# BB-shield-adapter.net
KiCad netlist of a schematic drawn in EAGLE
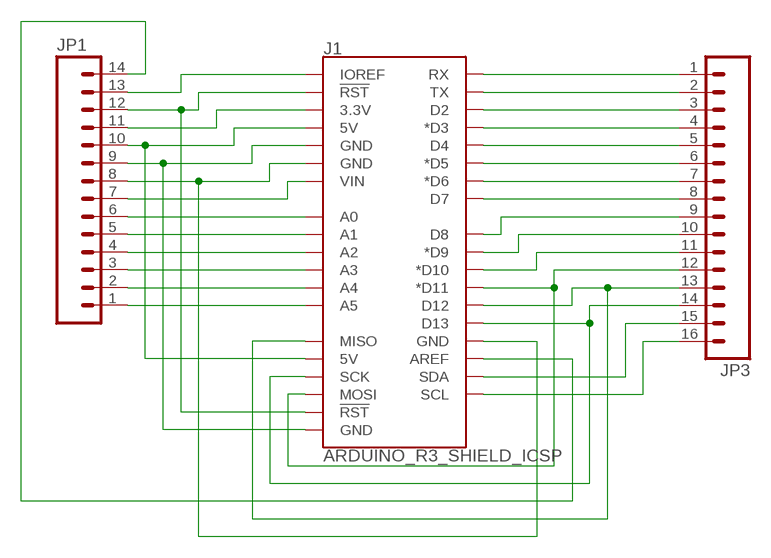
[diagram p0: schematic, sheet 1]

(export (version "E")
  (design (tool "Eeschema 10.0.6"))
  (components
    (comp (ref "J1")
      (value "ARDUINO_R3_SHIELD_ICSP")
      (footprint "eagle-import:UNO_R3_SHIELD_ICSP")
      (libsource (lib "eagle-import") (part "ARDUINO_R3_SHIELD_ICSP"))
    )
    (comp (ref "JP1")
      (value "M14")
      (footprint "eagle-import:1X14")
      (libsource (lib "eagle-import") (part "M14"))
    )
    (comp (ref "JP3")
      (value "M16PTH")
      (footprint "eagle-import:1X16")
      (libsource (lib "eagle-import") (part "M16PTH"))
    )
  )
  (nets
    (net (code "1") (name "Net-(J1-*D3)") (class "Default")
      (node (ref "J1") (pin "D3") (pinfunction "*D3_D3") (pintype "bidirectional"))
      (node (ref "JP3") (pin "4") (pinfunction "4_4") (pintype "passive"))
    )
    (net (code "2") (name "Net-(J1-*D5)") (class "Default")
      (node (ref "J1") (pin "D5") (pinfunction "*D5_D5") (pintype "bidirectional"))
      (node (ref "JP3") (pin "6") (pinfunction "6_6") (pintype "passive"))
    )
    (net (code "3") (name "Net-(J1-*D6)") (class "Default")
      (node (ref "J1") (pin "D6") (pinfunction "*D6_D6") (pintype "bidirectional"))
      (node (ref "JP3") (pin "7") (pinfunction "7_7") (pintype "passive"))
    )
    (net (code "4") (name "Net-(J1-*D9)") (class "Default")
      (node (ref "J1") (pin "D9") (pinfunction "*D9_D9") (pintype "bidirectional"))
      (node (ref "JP3") (pin "10") (pinfunction "10_10") (pintype "passive"))
    )
    (net (code "5") (name "Net-(J1-*D10)") (class "Default")
      (node (ref "J1") (pin "D10") (pinfunction "*D10_D10") (pintype "bidirectional"))
      (node (ref "JP3") (pin "11") (pinfunction "11_11") (pintype "passive"))
    )
    (net (code "6") (name "Net-(J1-*D11)") (class "Default")
      (node (ref "J1") (pin "D11") (pinfunction "*D11_D11") (pintype "bidirectional"))
      (node (ref "J1") (pin "MOSI") (pinfunction "MOSI_MOSI") (pintype "bidirectional"))
      (node (ref "JP3") (pin "12") (pinfunction "12_12") (pintype "passive"))
    )
    (net (code "7") (name "Net-(J1-5V-Pad5V_ICSP)") (class "Default")
      (node (ref "J1") (pin "5V") (pinfunction "5V_5V") (pintype "bidirectional"))
      (node (ref "J1") (pin "5V_ICSP") (pinfunction "5V_5V_ICSP") (pintype "bidirectional"))
      (node (ref "JP1") (pin "10") (pinfunction "10_10") (pintype "passive"))
    )
    (net (code "8") (name "Net-(J1-GND-PadGND@0)") (class "Default")
      (node (ref "J1") (pin "GND@0") (pinfunction "GND_GND@0") (pintype "bidirectional"))
      (node (ref "J1") (pin "GND_ICSP") (pinfunction "GND_GND_ICSP") (pintype "bidirectional"))
      (node (ref "JP1") (pin "9") (pinfunction "9_9") (pintype "passive"))
    )
    (net (code "9") (name "Net-(J1-GND-PadGND@1)") (class "Default")
      (node (ref "J1") (pin "GND@1") (pinfunction "GND_GND@1") (pintype "bidirectional"))
      (node (ref "J1") (pin "GND@2") (pinfunction "GND_GND@2") (pintype "bidirectional"))
      (node (ref "JP1") (pin "8") (pinfunction "8_8") (pintype "passive"))
    )
    (net (code "10") (name "Net-(J1-Pad3.3V)") (class "Default")
      (node (ref "J1") (pin "3.3V") (pinfunction "3.3V_3.3V") (pintype "bidirectional"))
      (node (ref "JP1") (pin "11") (pinfunction "11_11") (pintype "passive"))
    )
    (net (code "11") (name "Net-(J1-PadA0)") (class "Default")
      (node (ref "J1") (pin "A0") (pinfunction "A0_A0") (pintype "bidirectional"))
      (node (ref "JP1") (pin "6") (pinfunction "6_6") (pintype "passive"))
    )
    (net (code "12") (name "Net-(J1-PadA1)") (class "Default")
      (node (ref "J1") (pin "A1") (pinfunction "A1_A1") (pintype "bidirectional"))
      (node (ref "JP1") (pin "5") (pinfunction "5_5") (pintype "passive"))
    )
    (net (code "13") (name "Net-(J1-PadA2)") (class "Default")
      (node (ref "J1") (pin "A2") (pinfunction "A2_A2") (pintype "bidirectional"))
      (node (ref "JP1") (pin "4") (pinfunction "4_4") (pintype "passive"))
    )
    (net (code "14") (name "Net-(J1-PadA3)") (class "Default")
      (node (ref "J1") (pin "A3") (pinfunction "A3_A3") (pintype "bidirectional"))
      (node (ref "JP1") (pin "3") (pinfunction "3_3") (pintype "passive"))
    )
    (net (code "15") (name "Net-(J1-PadA4)") (class "Default")
      (node (ref "J1") (pin "A4") (pinfunction "A4_A4") (pintype "bidirectional"))
      (node (ref "JP1") (pin "2") (pinfunction "2_2") (pintype "passive"))
    )
    (net (code "16") (name "Net-(J1-PadA5)") (class "Default")
      (node (ref "J1") (pin "A5") (pinfunction "A5_A5") (pintype "bidirectional"))
      (node (ref "JP1") (pin "1") (pinfunction "1_1") (pintype "passive"))
    )
    (net (code "17") (name "Net-(J1-PadAREF)") (class "Default")
      (node (ref "J1") (pin "AREF") (pinfunction "AREF_AREF") (pintype "bidirectional"))
      (node (ref "JP1") (pin "14") (pinfunction "14_14") (pintype "passive"))
    )
    (net (code "18") (name "Net-(J1-PadD2)") (class "Default")
      (node (ref "J1") (pin "D2") (pinfunction "D2_D2") (pintype "bidirectional"))
      (node (ref "JP3") (pin "3") (pinfunction "3_3") (pintype "passive"))
    )
    (net (code "19") (name "Net-(J1-PadD4)") (class "Default")
      (node (ref "J1") (pin "D4") (pinfunction "D4_D4") (pintype "bidirectional"))
      (node (ref "JP3") (pin "5") (pinfunction "5_5") (pintype "passive"))
    )
    (net (code "20") (name "Net-(J1-PadD7)") (class "Default")
      (node (ref "J1") (pin "D7") (pinfunction "D7_D7") (pintype "bidirectional"))
      (node (ref "JP3") (pin "8") (pinfunction "8_8") (pintype "passive"))
    )
    (net (code "21") (name "Net-(J1-PadD8)") (class "Default")
      (node (ref "J1") (pin "D8") (pinfunction "D8_D8") (pintype "bidirectional"))
      (node (ref "JP3") (pin "9") (pinfunction "9_9") (pintype "passive"))
    )
    (net (code "22") (name "Net-(J1-PadD12)") (class "Default")
      (node (ref "J1") (pin "D12") (pinfunction "D12_D12") (pintype "bidirectional"))
      (node (ref "J1") (pin "MISO") (pinfunction "MISO_MISO") (pintype "bidirectional"))
      (node (ref "JP3") (pin "13") (pinfunction "13_13") (pintype "passive"))
    )
    (net (code "23") (name "Net-(J1-PadD13)") (class "Default")
      (node (ref "J1") (pin "D13") (pinfunction "D13_D13") (pintype "bidirectional"))
      (node (ref "J1") (pin "SCK") (pinfunction "SCK_SCK") (pintype "bidirectional"))
      (node (ref "JP3") (pin "14") (pinfunction "14_14") (pintype "passive"))
    )
    (net (code "24") (name "Net-(J1-PadIOREF)") (class "Default")
      (node (ref "J1") (pin "IOREF") (pinfunction "IOREF_IOREF") (pintype "bidirectional"))
      (node (ref "JP1") (pin "13") (pinfunction "13_13") (pintype "passive"))
    )
    (net (code "25") (name "Net-(J1-PadRX)") (class "Default")
      (node (ref "J1") (pin "RX") (pinfunction "RX_RX") (pintype "bidirectional"))
      (node (ref "JP3") (pin "1") (pinfunction "1_1") (pintype "passive"))
    )
    (net (code "26") (name "Net-(J1-PadSCL)") (class "Default")
      (node (ref "J1") (pin "SCL") (pinfunction "SCL_SCL") (pintype "bidirectional"))
      (node (ref "JP3") (pin "16") (pinfunction "16_16") (pintype "passive"))
    )
    (net (code "27") (name "Net-(J1-PadSDA)") (class "Default")
      (node (ref "J1") (pin "SDA") (pinfunction "SDA_SDA") (pintype "bidirectional"))
      (node (ref "JP3") (pin "15") (pinfunction "15_15") (pintype "passive"))
    )
    (net (code "28") (name "Net-(J1-PadTX)") (class "Default")
      (node (ref "J1") (pin "TX") (pinfunction "TX_TX") (pintype "bidirectional"))
      (node (ref "JP3") (pin "2") (pinfunction "2_2") (pintype "passive"))
    )
    (net (code "29") (name "Net-(J1-PadVIN)") (class "Default")
      (node (ref "J1") (pin "VIN") (pinfunction "VIN_VIN") (pintype "bidirectional"))
      (node (ref "JP1") (pin "7") (pinfunction "7_7") (pintype "passive"))
    )
    (net (code "30") (name "Net-(J1-~{RST}-PadRES)") (class "Default")
      (node (ref "J1") (pin "RES") (pinfunction "~{RST}_RES") (pintype "bidirectional"))
      (node (ref "J1") (pin "RST_ICSP") (pinfunction "~{RST}_RST_ICSP") (pintype "bidirectional"))
      (node (ref "JP1") (pin "12") (pinfunction "12_12") (pintype "passive"))
    )
  )
)
